# Sheet1.net
KiCad netlist of a schematic drawn in Altium Designer
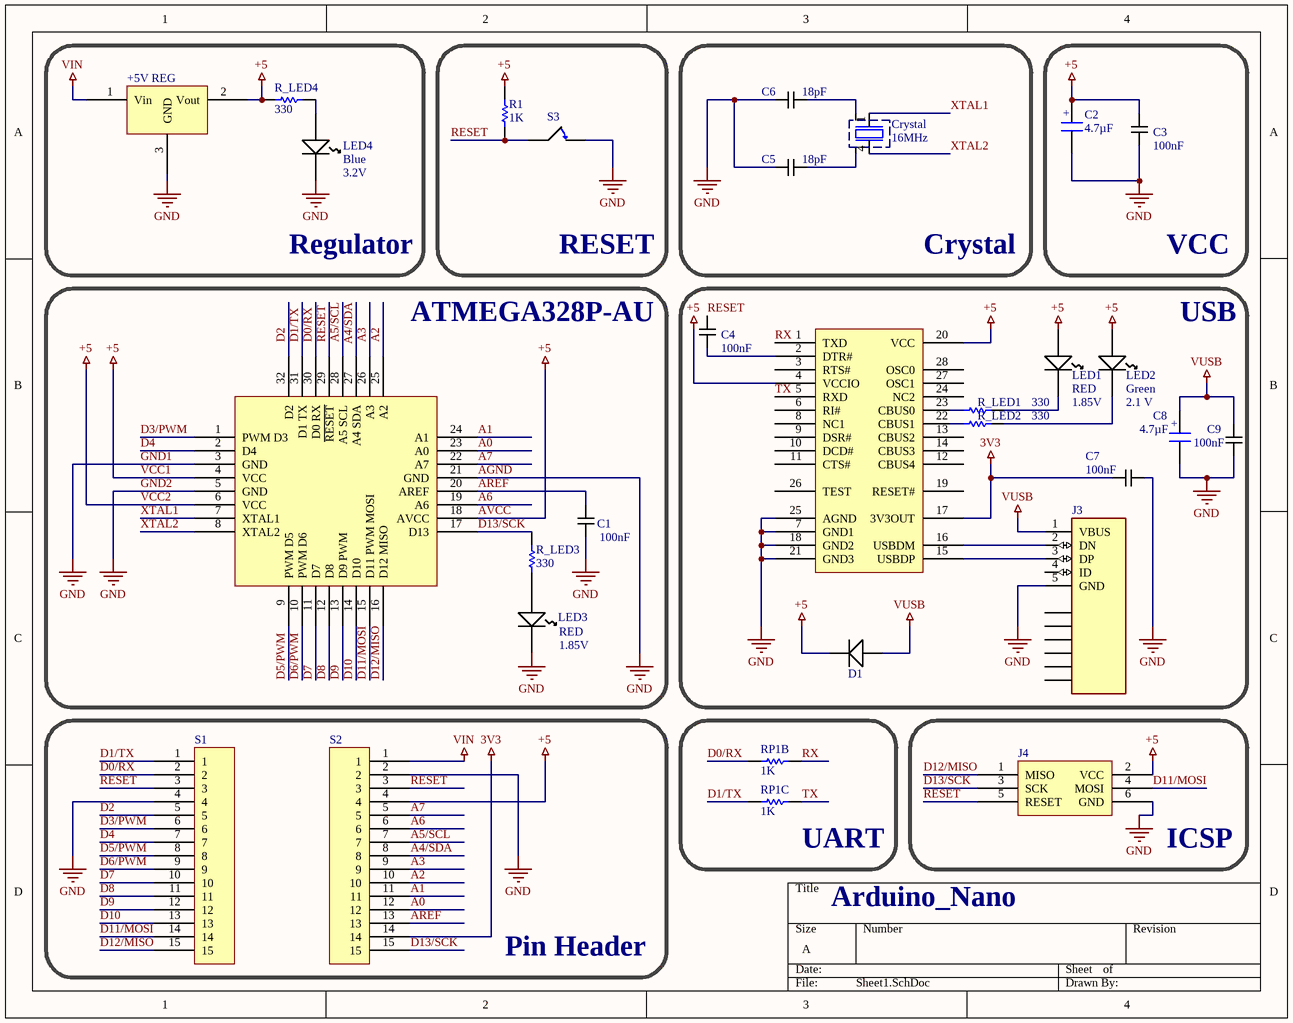
[diagram p0: Sheet1.SchDoc]

(export (version "E")
  (design (tool "Eeschema 10.0.6"))
  (components
    (comp (ref "+5V REG")
      (value "LM1117MP-5.0/NOPB, Low Dropout Voltage Regulator, 1.5A, 5 V ±1%, 4-Pin SOT-223")
      (footprint "SOT230P700X180-4N")
      (fields (field (name "MANUFACTURER") "Texas Instruments") (field (name "CREATED BY") "R Kanjee"))
      (libsource (lib "TI Low Dropout Voltage Regulator") (part "LM1117MP-5.0"))
    )
    (comp (ref "C1")
      (value "100nF Ceramic Multilayer Capacitor_1")
      (footprint "CAPCP2012X09N")
      (description "AVX 0805 Standard 100nF Ceramic Multilayer Capacitor, 50 V dc X7R Dielectric ±10% SMD")
      (fields
        (field (name "MANUFACTURER") "AVX")
        (field (name "VOLTAGE") "50V")
        (field (name "CAPACITANCE") "100nF")
        (field (name "CREATOR") "Ritesh Kanjee")
      )
      (libsource (lib "RS Components - Capacitors") (part "100nF Ceramic Multilayer Capacitor_1"))
    )
    (comp (ref "C2")
      (value "4.7µF")
      (footprint "CASE A - 3216X18")
      (description "Capacitor,tantalum,SMT,16V,4.7uF,10%,A-case")
      (fields
        (field (name "TOLERANCE") "10%")
        (field (name "VOLTAGE") "16V")
        (field (name "PUBLISHER") "DPSS")
      )
      (libsource (lib "RS Components - Capacitors") (part "4.7µF Tant RS 496-3545"))
    )
    (comp (ref "C3")
      (value "100nF Ceramic Multilayer Capacitor_1")
      (footprint "CAPCP2012X09N")
      (description "AVX 0805 Standard 100nF Ceramic Multilayer Capacitor, 50 V dc X7R Dielectric ±10% SMD")
      (fields
        (field (name "MANUFACTURER") "AVX")
        (field (name "VOLTAGE") "50V")
        (field (name "CAPACITANCE") "100nF")
        (field (name "CREATOR") "Ritesh Kanjee")
      )
      (libsource (lib "RS Components - Capacitors") (part "100nF Ceramic Multilayer Capacitor_1"))
    )
    (comp (ref "C4")
      (value "100nF Ceramic Multilayer Capacitor_1")
      (footprint "CAPCP2012X09N")
      (description "AVX 0805 Standard 100nF Ceramic Multilayer Capacitor, 50 V dc X7R Dielectric ±10% SMD")
      (fields
        (field (name "MANUFACTURER") "AVX")
        (field (name "VOLTAGE") "50V")
        (field (name "CAPACITANCE") "100nF")
        (field (name "CREATOR") "Ritesh Kanjee")
      )
      (libsource (lib "RS Components - Capacitors") (part "100nF Ceramic Multilayer Capacitor_1"))
    )
    (comp (ref "C5")
      (value "C0805C180J5GACTU")
      (footprint "CAPCP2012X09N")
      (description "18pF Ceramic Multilayer Capacitor, 50 V dc C0G Dielectric ±5% SMD")
      (fields
        (field (name "MANUFACTURER") "Kemet")
        (field (name "VOLTAGE") "50V")
        (field (name "CAPACITANCE") "18pF")
        (field (name "CREATOR") "Ritesh Kanjee")
      )
      (libsource (lib "RS Components - Capacitors") (part "18pF Ceramic Multilayer Capacitor, 50 V dc C0G Dielectric ±5% SMD"))
    )
    (comp (ref "C6")
      (value "C0805C180J5GACTU")
      (footprint "CAPCP2012X09N")
      (description "18pF Ceramic Multilayer Capacitor, 50 V dc C0G Dielectric ±5% SMD")
      (fields
        (field (name "MANUFACTURER") "Kemet")
        (field (name "VOLTAGE") "50V")
        (field (name "CAPACITANCE") "18pF")
        (field (name "CREATOR") "Ritesh Kanjee")
      )
      (libsource (lib "RS Components - Capacitors") (part "18pF Ceramic Multilayer Capacitor, 50 V dc C0G Dielectric ±5% SMD"))
    )
    (comp (ref "C7")
      (value "100nF Ceramic Multilayer Capacitor_1")
      (footprint "CAPCP2012X09N")
      (description "AVX 0805 Standard 100nF Ceramic Multilayer Capacitor, 50 V dc X7R Dielectric ±10% SMD")
      (fields
        (field (name "MANUFACTURER") "AVX")
        (field (name "VOLTAGE") "50V")
        (field (name "CAPACITANCE") "100nF")
        (field (name "CREATOR") "Ritesh Kanjee")
      )
      (libsource (lib "RS Components - Capacitors") (part "100nF Ceramic Multilayer Capacitor_1"))
    )
    (comp (ref "C8")
      (value "4.7µF")
      (footprint "CASE A - 3216X18")
      (description "Capacitor,tantalum,SMT,16V,4.7uF,10%,A-case")
      (fields
        (field (name "TOLERANCE") "10%")
        (field (name "VOLTAGE") "16V")
        (field (name "PUBLISHER") "DPSS")
      )
      (libsource (lib "RS Components - Capacitors") (part "4.7µF Tant RS 496-3545"))
    )
    (comp (ref "C9")
      (value "100nF Ceramic Multilayer Capacitor_1")
      (footprint "CAPCP2012X09N")
      (description "AVX 0805 Standard 100nF Ceramic Multilayer Capacitor, 50 V dc X7R Dielectric ±10% SMD")
      (fields
        (field (name "MANUFACTURER") "AVX")
        (field (name "VOLTAGE") "50V")
        (field (name "CAPACITANCE") "100nF")
        (field (name "CREATOR") "Ritesh Kanjee")
      )
      (libsource (lib "RS Components - Capacitors") (part "100nF Ceramic Multilayer Capacitor_1"))
    )
    (comp (ref "Crystal")
      (value "16MHz")
      (footprint "Aker S5C Crystal")
      (description "Aker S5C SMT Crystal")
      (fields
        (field (name "MANUFACTURER") "Aker")
        (field (name "MANUFACTURER PART #") "C5S-16.000-12-3030-X")
        (field (name "CREATOR") "R Kanjee")
      )
      (libsource (lib "Aker Crystals") (part "Aker  C5S-16.000-12-3030-X"))
    )
    (comp (ref "D1")
      (value "Panasonic DB2J20900L Schottky Diode, 0.5A, 20V, 2.4ns, 2-Pin SMini2 F5 B")
      (footprint "DIOM1712X07N")
      (fields
        (field (name "MANUFACTURER") "Panasonic")
        (field (name "MANUFACTURER PART NO.") "DB2J20900L")
        (field (name "CREATED BY") "R Kanjee")
      )
      (libsource (lib "Panasonic Diodes") (part "Schottky Diode, 0.5A, 20V, 2.4ns, 2-Pin SMini2 F5 B"))
    )
    (comp (ref "J3")
      (value "2013499-1")
      (footprint "TE_2013499-1")
      (libsource (lib "2013499-1") (part "2013499-1"))
    )
    (comp (ref "J4")
      (value "Programming Headers Dual Row")
      (footprint "ISP HEADER")
      (fields
        (field (name "MANUFACTURER") "FCI")
        (field (name "MANUFACTURER PART NO.") "68000-236HLF")
        (field (name "CREATED BY") "R Kanjee")
      )
      (libsource (lib "PCB Headers") (part "Programming ISP, Programming Headers Dual Row"))
    )
    (comp (ref "LED1")
      (value "Kingbright Red LED, 100 mcd 120 ° 0805")
      (footprint "LED1913X12NRED")
      (fields
        (field (name "MANUFACTURER") "KingBright")
        (field (name "MANUFACTURER PART NO.") "KP-2012SRC-PRV")
        (field (name "COLOR") "RED")
        (field (name "FORWARD VOLTAGE") "1.85V")
        (field (name "CREATOR") "Ritesh Kanjee")
      )
      (libsource (lib "KingBright LEDs") (part "Kingbright Red LED, 100 mcd 120 ° 0805"))
    )
    (comp (ref "LED2")
      (value "Kingbright Green LED, 70 mcd 120 ° 0805")
      (footprint "LED1913X12NGREEN")
      (fields
        (field (name "MANUFACTURER") "KingBright")
        (field (name "MANUFACTURER PART NO.") "KP-2012MGC")
        (field (name "COLOR") "Green")
        (field (name "FORWARD VOLTAGE") "2.1 V")
        (field (name "CREATOR") "Ritesh Kanjee")
      )
      (libsource (lib "KingBright LEDs") (part "Kingbright Green LED, 70 mcd 120 ° 0805"))
    )
    (comp (ref "LED3")
      (value "Kingbright Red LED, 100 mcd 120 ° 0805")
      (footprint "LED1913X12NRED")
      (fields
        (field (name "MANUFACTURER") "KingBright")
        (field (name "MANUFACTURER PART NO.") "KP-2012SRC-PRV")
        (field (name "COLOR") "RED")
        (field (name "FORWARD VOLTAGE") "1.85V")
        (field (name "CREATOR") "Ritesh Kanjee")
      )
      (libsource (lib "KingBright LEDs") (part "Kingbright Red LED, 100 mcd 120 ° 0805"))
    )
    (comp (ref "LED4")
      (value "Kingbright Blue LED, 60 mcd 120 ° 0805")
      (footprint "LED1913X12NBLUE")
      (fields
        (field (name "MANUFACTURER") "KingBright")
        (field (name "MANUFACTURER PART NO.") "KP-2012PBC-A")
        (field (name "COLOR") "Blue")
        (field (name "FORWARD VOLTAGE") "3.2V")
        (field (name "CREATOR") "Ritesh Kanjee")
      )
      (libsource (lib "KingBright LEDs") (part "Kingbright Blue LED, 60 mcd 120 ° 0805"))
    )
    (comp (ref "MicroController")
      (value "ATMEGA328P-AU")
      (footprint "TQFP80P900X900X120-32N")
      (description "ATMEGA328P-AU, 8 bit AVR Microcontroller 20MHz 1 kB, 32 kB Flash, 2 kB RAM, I2C 32-Pin TQFP")
      (fields (field (name "CREATED BY") "Ritesh Kanjee"))
      (libsource (lib "Atmel Microcontrollers") (part "ATMEGA328P-AU"))
    )
    (comp (ref "R1")
      (value "1K")
      (description "Resistor")
      (libsource (lib "Simulation Generic Components") (part "Resistor"))
    )
    (comp (ref "RP1B")
      (value "1K")
      (description "Resistor")
      (libsource (lib "Simulation Generic Components") (part "Resistor"))
    )
    (comp (ref "RP1C")
      (value "1K")
      (description "Resistor")
      (libsource (lib "Simulation Generic Components") (part "Resistor"))
    )
    (comp (ref "R_LED1")
      (value "330")
      (description "Resistor")
      (libsource (lib "Simulation Generic Components") (part "Resistor"))
    )
    (comp (ref "R_LED2")
      (value "330")
      (description "Resistor")
      (libsource (lib "Simulation Generic Components") (part "Resistor"))
    )
    (comp (ref "R_LED3")
      (value "330")
      (description "Resistor")
      (libsource (lib "Simulation Generic Components") (part "Resistor"))
    )
    (comp (ref "R_LED4")
      (value "330")
      (description "Resistor")
      (libsource (lib "Simulation Generic Components") (part "Resistor"))
    )
    (comp (ref "S1")
      (value "connector;str header;single row;.1 cont centers;.095 tail;gold or gtx;36 contact")
      (footprint "Header")
      (fields
        (field (name "MANUFACTURER") "FCI")
        (field (name "MANUFACTURER PART NO.") "68000-236HLF")
        (field (name "CREATED BY") "R Kanjee")
      )
      (libsource (lib "") (part "Single row; PCB headers_1"))
    )
    (comp (ref "S2")
      (value "connector;str header;single row;.1 cont centers;.095 tail;gold or gtx;36 contact")
      (footprint "Header")
      (fields
        (field (name "MANUFACTURER") "FCI")
        (field (name "MANUFACTURER PART NO.") "68000-236HLF")
        (field (name "CREATED BY") "R Kanjee")
      )
      (libsource (lib "PCB Headers") (part "Single row; PCB headers"))
    )
    (comp (ref "S3")
      (value "Button Tactile Switch, NO 0.05 A 0.8mm")
      (footprint "Button8014X17N")
      (fields
        (field (name "MANUFACTURER") "C & K")
        (field (name "MANUFACTURER PART NO.") "B3F1000")
        (field (name "CREATOR") "R Kanjee")
      )
      (libsource (lib "Omron Tactile Switches") (part "Button Tactile Switch, NO 0.05 A 0.8mm"))
    )
    (comp (ref "USB")
      (value "FT232RL, Universal Asynchronous Receiver & Transmitter 3MBd, 28-Pin, SSOP")
      (footprint "SOP65P780X200-28N")
      (fields
        (field (name "MANUFACTURER PART NO.") "FT232RL")
        (field (name "MANUFACTURER") "FTDI Chip")
        (field (name "CREATOR") "R Kanjee")
      )
      (libsource (lib "FTDI RS232toUSB") (part "FT232RL USB to UART, Universal Asynchronous Receiver & Transmitter 3MBd, 28-Pin, SSOP"))
    )
  )
  (nets
    (net (code "1") (name "+5") (class "Default")
      (node (ref "+5V REG") (pin "2") (pinfunction "Vout_2") (pintype "passive"))
      (node (ref "C2") (pin "1") (pinfunction "1_1") (pintype "passive"))
      (node (ref "C3") (pin "2") (pinfunction "2_2") (pintype "passive"))
      (node (ref "D1") (pin "1") (pinfunction "1_1") (pintype "passive"))
      (node (ref "J4") (pin "2") (pinfunction "VCC_2") (pintype "passive"))
      (node (ref "LED1") (pin "1") (pinfunction "A_1") (pintype "passive"))
      (node (ref "LED2") (pin "1") (pinfunction "A_1") (pintype "passive"))
      (node (ref "MicroController") (pin "18") (pinfunction "AVCC_18") (pintype "passive"))
      (node (ref "MicroController") (pin "4") (pinfunction "VCC_4") (pintype "passive"))
      (node (ref "MicroController") (pin "6") (pinfunction "VCC_6") (pintype "passive"))
      (node (ref "R1") (pin "2") (pinfunction "2_2") (pintype "passive"))
      (node (ref "R_LED4") (pin "1") (pinfunction "1_1") (pintype "passive"))
      (node (ref "S2") (pin "4") (pinfunction "4_4") (pintype "passive"))
      (node (ref "USB") (pin "20") (pinfunction "VCC_20") (pintype "passive"))
      (node (ref "USB") (pin "4") (pinfunction "VCCIO_4") (pintype "passive"))
    )
    (net (code "2") (name "/A0") (class "Default")
      (node (ref "MicroController") (pin "23") (pinfunction "A0_23") (pintype "passive"))
      (node (ref "S2") (pin "12") (pinfunction "12_12") (pintype "passive"))
    )
    (net (code "3") (name "/A1") (class "Default")
      (node (ref "MicroController") (pin "24") (pinfunction "A1_24") (pintype "passive"))
      (node (ref "S2") (pin "11") (pinfunction "11_11") (pintype "passive"))
    )
    (net (code "4") (name "/A2") (class "Default")
      (node (ref "MicroController") (pin "25") (pinfunction "A2_25") (pintype "passive"))
      (node (ref "S2") (pin "10") (pinfunction "10_10") (pintype "passive"))
    )
    (net (code "5") (name "/A3") (class "Default")
      (node (ref "MicroController") (pin "26") (pinfunction "A3_26") (pintype "passive"))
      (node (ref "S2") (pin "9") (pinfunction "9_9") (pintype "passive"))
    )
    (net (code "6") (name "/A4{slash}SDA") (class "Default")
      (node (ref "MicroController") (pin "27") (pinfunction "A4_SDA_27") (pintype "passive"))
      (node (ref "S2") (pin "8") (pinfunction "8_8") (pintype "passive"))
    )
    (net (code "7") (name "/A5{slash}SCL") (class "Default")
      (node (ref "MicroController") (pin "28") (pinfunction "A5_SCL_28") (pintype "passive"))
      (node (ref "S2") (pin "7") (pinfunction "7_7") (pintype "passive"))
    )
    (net (code "8") (name "/A6") (class "Default")
      (node (ref "MicroController") (pin "19") (pinfunction "A6_19") (pintype "passive"))
      (node (ref "S2") (pin "6") (pinfunction "6_6") (pintype "passive"))
    )
    (net (code "9") (name "/A7") (class "Default")
      (node (ref "MicroController") (pin "22") (pinfunction "A7_22") (pintype "passive"))
      (node (ref "S2") (pin "5") (pinfunction "5_5") (pintype "passive"))
    )
    (net (code "10") (name "/AREF") (class "Default")
      (node (ref "C1") (pin "2") (pinfunction "2_2") (pintype "passive"))
      (node (ref "MicroController") (pin "20") (pinfunction "AREF_20") (pintype "passive"))
      (node (ref "S2") (pin "13") (pinfunction "13_13") (pintype "passive"))
    )
    (net (code "11") (name "/D0{slash}RX") (class "Default")
      (node (ref "MicroController") (pin "30") (pinfunction "D0_RX_30") (pintype "passive"))
      (node (ref "RP1B") (pin "1") (pinfunction "1_1") (pintype "passive"))
      (node (ref "S1") (pin "2") (pinfunction "2_2") (pintype "passive"))
    )
    (net (code "12") (name "/D1{slash}TX") (class "Default")
      (node (ref "MicroController") (pin "31") (pinfunction "D1_TX_31") (pintype "passive"))
      (node (ref "RP1C") (pin "1") (pinfunction "1_1") (pintype "passive"))
      (node (ref "S1") (pin "1") (pinfunction "1_1") (pintype "passive"))
    )
    (net (code "13") (name "/D2") (class "Default")
      (node (ref "MicroController") (pin "32") (pinfunction "D2_32") (pintype "passive"))
      (node (ref "S1") (pin "5") (pinfunction "5_5") (pintype "passive"))
    )
    (net (code "14") (name "/D3{slash}PWM") (class "Default")
      (node (ref "MicroController") (pin "1") (pinfunction "PWM_D3_1") (pintype "passive"))
      (node (ref "S1") (pin "6") (pinfunction "6_6") (pintype "passive"))
    )
    (net (code "15") (name "/D4") (class "Default")
      (node (ref "MicroController") (pin "2") (pinfunction "D4_2") (pintype "passive"))
      (node (ref "S1") (pin "7") (pinfunction "7_7") (pintype "passive"))
    )
    (net (code "16") (name "/D5{slash}PWM") (class "Default")
      (node (ref "MicroController") (pin "9") (pinfunction "PWM_D5_9") (pintype "passive"))
      (node (ref "S1") (pin "8") (pinfunction "8_8") (pintype "passive"))
    )
    (net (code "17") (name "/D6{slash}PWM") (class "Default")
      (node (ref "MicroController") (pin "10") (pinfunction "PWM_D6_10") (pintype "passive"))
      (node (ref "S1") (pin "9") (pinfunction "9_9") (pintype "passive"))
    )
    (net (code "18") (name "/D7") (class "Default")
      (node (ref "MicroController") (pin "11") (pinfunction "D7_11") (pintype "passive"))
      (node (ref "S1") (pin "10") (pinfunction "10_10") (pintype "passive"))
    )
    (net (code "19") (name "/D8") (class "Default")
      (node (ref "MicroController") (pin "12") (pinfunction "D8_12") (pintype "passive"))
      (node (ref "S1") (pin "11") (pinfunction "11_11") (pintype "passive"))
    )
    (net (code "20") (name "/D9") (class "Default")
      (node (ref "MicroController") (pin "13") (pinfunction "D9_PWM_13") (pintype "passive"))
      (node (ref "S1") (pin "12") (pinfunction "12_12") (pintype "passive"))
    )
    (net (code "21") (name "/D10") (class "Default")
      (node (ref "MicroController") (pin "14") (pinfunction "D10_14") (pintype "passive"))
      (node (ref "S1") (pin "13") (pinfunction "13_13") (pintype "passive"))
    )
    (net (code "22") (name "/D11{slash}MOSI") (class "Default")
      (node (ref "J4") (pin "4") (pinfunction "MOSI_4") (pintype "passive"))
      (node (ref "MicroController") (pin "15") (pinfunction "D11_PWM_MOSI_15") (pintype "passive"))
      (node (ref "S1") (pin "14") (pinfunction "14_14") (pintype "passive"))
    )
    (net (code "23") (name "/D12{slash}MISO") (class "Default")
      (node (ref "J4") (pin "1") (pinfunction "MISO_1") (pintype "passive"))
      (node (ref "MicroController") (pin "16") (pinfunction "D12_MISO_16") (pintype "passive"))
      (node (ref "S1") (pin "15") (pinfunction "15_15") (pintype "passive"))
    )
    (net (code "24") (name "/D13{slash}SCK") (class "Default")
      (node (ref "J4") (pin "3") (pinfunction "SCK_3") (pintype "passive"))
      (node (ref "MicroController") (pin "17") (pinfunction "D13_17") (pintype "passive"))
      (node (ref "R_LED3") (pin "2") (pinfunction "2_2") (pintype "passive"))
      (node (ref "S2") (pin "15") (pinfunction "15_15") (pintype "passive"))
    )
    (net (code "25") (name "/RESET") (class "Default")
      (node (ref "C4") (pin "2") (pinfunction "2_2") (pintype "passive"))
      (node (ref "J4") (pin "5") (pinfunction "RESET_5") (pintype "passive"))
      (node (ref "MicroController") (pin "29") (pinfunction "~{RESET}_29") (pintype "passive"))
      (node (ref "R1") (pin "1") (pinfunction "1_1") (pintype "passive"))
      (node (ref "S1") (pin "3") (pinfunction "3_3") (pintype "passive"))
      (node (ref "S2") (pin "3") (pinfunction "3_3") (pintype "passive"))
      (node (ref "S3") (pin "1") (pinfunction "1_1") (pintype "passive"))
    )
    (net (code "26") (name "/RX") (class "Default")
      (node (ref "RP1B") (pin "2") (pinfunction "2_2") (pintype "passive"))
      (node (ref "USB") (pin "1") (pinfunction "TXD_1") (pintype "passive"))
    )
    (net (code "27") (name "/TX") (class "Default")
      (node (ref "RP1C") (pin "2") (pinfunction "2_2") (pintype "passive"))
      (node (ref "USB") (pin "5") (pinfunction "RXD_5") (pintype "passive"))
    )
    (net (code "28") (name "/XTAL1") (class "Default")
      (node (ref "Crystal") (pin "1") (pinfunction "1_1") (pintype "passive"))
      (node (ref "MicroController") (pin "7") (pinfunction "XTAL1_7") (pintype "passive"))
    )
    (net (code "29") (name "/XTAL2") (class "Default")
      (node (ref "Crystal") (pin "4") (pinfunction "4_4") (pintype "passive"))
      (node (ref "MicroController") (pin "8") (pinfunction "XTAL2_8") (pintype "passive"))
    )
    (net (code "30") (name "3V3") (class "Default")
      (node (ref "C7") (pin "1") (pinfunction "1_1") (pintype "passive"))
      (node (ref "S2") (pin "14") (pinfunction "14_14") (pintype "passive"))
      (node (ref "USB") (pin "17") (pinfunction "3V3OUT_17") (pintype "passive"))
    )
    (net (code "31") (name "GND") (class "Default")
      (node (ref "+5V REG") (pin "3") (pinfunction "GND_3") (pintype "passive"))
      (node (ref "C1") (pin "1") (pinfunction "1_1") (pintype "passive"))
      (node (ref "C2") (pin "2") (pinfunction "2_2") (pintype "passive"))
      (node (ref "C3") (pin "1") (pinfunction "1_1") (pintype "passive"))
      (node (ref "C5") (pin "2") (pinfunction "2_2") (pintype "passive"))
      (node (ref "C6") (pin "2") (pinfunction "2_2") (pintype "passive"))
      (node (ref "C7") (pin "2") (pinfunction "2_2") (pintype "passive"))
      (node (ref "C8") (pin "2") (pinfunction "2_2") (pintype "passive"))
      (node (ref "C9") (pin "1") (pinfunction "1_1") (pintype "passive"))
      (node (ref "J3") (pin "5") (pinfunction "GND_5") (pintype "power_in"))
      (node (ref "J4") (pin "6") (pinfunction "GND_6") (pintype "passive"))
      (node (ref "LED3") (pin "2") (pinfunction "K_2") (pintype "passive"))
      (node (ref "LED4") (pin "2") (pinfunction "K_2") (pintype "passive"))
      (node (ref "MicroController") (pin "21") (pinfunction "GND_21") (pintype "passive"))
      (node (ref "MicroController") (pin "3") (pinfunction "GND_3") (pintype "passive"))
      (node (ref "MicroController") (pin "5") (pinfunction "GND_5") (pintype "passive"))
      (node (ref "S1") (pin "4") (pinfunction "4_4") (pintype "passive"))
      (node (ref "S2") (pin "2") (pinfunction "2_2") (pintype "passive"))
      (node (ref "S3") (pin "1") (pinfunction "1_1") (pintype "passive"))
      (node (ref "USB") (pin "18") (pinfunction "GND2_18") (pintype "passive"))
      (node (ref "USB") (pin "21") (pinfunction "GND3_21") (pintype "passive"))
      (node (ref "USB") (pin "25") (pinfunction "AGND_25") (pintype "passive"))
      (node (ref "USB") (pin "7") (pinfunction "GND1_7") (pintype "passive"))
    )
    (net (code "32") (name "Net-(C5-Pad1)") (class "Default")
      (node (ref "C5") (pin "1") (pinfunction "1_1") (pintype "passive"))
      (node (ref "Crystal") (pin "2") (pinfunction "Gnd_2") (pintype "power_in"))
    )
    (net (code "33") (name "Net-(C6-Pad1)") (class "Default")
      (node (ref "C6") (pin "1") (pinfunction "1_1") (pintype "passive"))
      (node (ref "Crystal") (pin "3") (pinfunction "Gnd_3") (pintype "power_in"))
    )
    (net (code "34") (name "Net-(J3-DN)") (class "Default")
      (node (ref "J3") (pin "2") (pinfunction "DN_2") (pintype "bidirectional"))
      (node (ref "USB") (pin "16") (pinfunction "USBDM_16") (pintype "passive"))
    )
    (net (code "35") (name "Net-(J3-DP)") (class "Default")
      (node (ref "J3") (pin "3") (pinfunction "DP_3") (pintype "bidirectional"))
      (node (ref "USB") (pin "15") (pinfunction "USBDP_15") (pintype "passive"))
    )
    (net (code "36") (name "Net-(LED1-K)") (class "Default")
      (node (ref "LED1") (pin "2") (pinfunction "K_2") (pintype "passive"))
      (node (ref "R_LED1") (pin "1") (pinfunction "1_1") (pintype "passive"))
    )
    (net (code "37") (name "Net-(LED2-K)") (class "Default")
      (node (ref "LED2") (pin "2") (pinfunction "K_2") (pintype "passive"))
      (node (ref "R_LED2") (pin "1") (pinfunction "1_1") (pintype "passive"))
    )
    (net (code "38") (name "Net-(LED3-A)") (class "Default")
      (node (ref "LED3") (pin "1") (pinfunction "A_1") (pintype "passive"))
      (node (ref "R_LED3") (pin "1") (pinfunction "1_1") (pintype "passive"))
    )
    (net (code "39") (name "Net-(LED4-A)") (class "Default")
      (node (ref "LED4") (pin "1") (pinfunction "A_1") (pintype "passive"))
      (node (ref "R_LED4") (pin "2") (pinfunction "2_2") (pintype "passive"))
    )
    (net (code "40") (name "Net-(USB-CBUS0)") (class "Default")
      (node (ref "R_LED1") (pin "2") (pinfunction "2_2") (pintype "passive"))
      (node (ref "USB") (pin "23") (pinfunction "CBUS0_23") (pintype "passive"))
    )
    (net (code "41") (name "Net-(USB-CBUS1)") (class "Default")
      (node (ref "R_LED2") (pin "2") (pinfunction "2_2") (pintype "passive"))
      (node (ref "USB") (pin "22") (pinfunction "CBUS1_22") (pintype "passive"))
    )
    (net (code "42") (name "Net-(USB-DTR#)") (class "Default")
      (node (ref "C4") (pin "1") (pinfunction "1_1") (pintype "passive"))
      (node (ref "USB") (pin "2") (pinfunction "DTR#_2") (pintype "passive"))
    )
    (net (code "43") (name "VIN") (class "Default")
      (node (ref "+5V REG") (pin "1") (pinfunction "Vin_1") (pintype "passive"))
      (node (ref "S2") (pin "1") (pinfunction "1_1") (pintype "passive"))
    )
    (net (code "44") (name "VUSB") (class "Default")
      (node (ref "C8") (pin "1") (pinfunction "1_1") (pintype "passive"))
      (node (ref "C9") (pin "2") (pinfunction "2_2") (pintype "passive"))
      (node (ref "D1") (pin "2") (pinfunction "2_2") (pintype "passive"))
      (node (ref "J3") (pin "1") (pinfunction "VBUS_1") (pintype "power_in"))
    )
    (net (code "45") (name "unconnected-(J3-ID-Pad4)") (class "Default")
      (node (ref "J3") (pin "4") (pinfunction "ID_4") (pintype "bidirectional"))
    )
    (net (code "46") (name "unconnected-(J3-SHIELD-PadSH1)") (class "Default")
      (node (ref "J3") (pin "SH1") (pinfunction "SHIELD_SH1") (pintype "passive"))
    )
    (net (code "47") (name "unconnected-(J3-SHIELD-PadSH2)") (class "Default")
      (node (ref "J3") (pin "SH2") (pinfunction "SHIELD_SH2") (pintype "passive"))
    )
    (net (code "48") (name "unconnected-(J3-SHIELD-PadSH3)") (class "Default")
      (node (ref "J3") (pin "SH3") (pinfunction "SHIELD_SH3") (pintype "passive"))
    )
    (net (code "49") (name "unconnected-(J3-SHIELD-PadSH4)") (class "Default")
      (node (ref "J3") (pin "SH4") (pinfunction "SHIELD_SH4") (pintype "passive"))
    )
    (net (code "50") (name "unconnected-(J3-SHIELD-PadSH5)") (class "Default")
      (node (ref "J3") (pin "SH5") (pinfunction "SHIELD_SH5") (pintype "passive"))
    )
    (net (code "51") (name "unconnected-(J3-SHIELD-PadSH6)") (class "Default")
      (node (ref "J3") (pin "SH6") (pinfunction "SHIELD_SH6") (pintype "passive"))
    )
    (net (code "52") (name "unconnected-(USB-CBUS2-Pad13)") (class "Default")
      (node (ref "USB") (pin "13") (pinfunction "CBUS2_13") (pintype "passive"))
    )
    (net (code "53") (name "unconnected-(USB-CBUS3-Pad14)") (class "Default")
      (node (ref "USB") (pin "14") (pinfunction "CBUS3_14") (pintype "passive"))
    )
    (net (code "54") (name "unconnected-(USB-CBUS4-Pad12)") (class "Default")
      (node (ref "USB") (pin "12") (pinfunction "CBUS4_12") (pintype "passive"))
    )
    (net (code "55") (name "unconnected-(USB-CTS#-Pad11)") (class "Default")
      (node (ref "USB") (pin "11") (pinfunction "CTS#_11") (pintype "passive"))
    )
    (net (code "56") (name "unconnected-(USB-DCD#-Pad10)") (class "Default")
      (node (ref "USB") (pin "10") (pinfunction "DCD#_10") (pintype "passive"))
    )
    (net (code "57") (name "unconnected-(USB-DSR#-Pad9)") (class "Default")
      (node (ref "USB") (pin "9") (pinfunction "DSR#_9") (pintype "passive"))
    )
    (net (code "58") (name "unconnected-(USB-NC1-Pad8)") (class "Default")
      (node (ref "USB") (pin "8") (pinfunction "NC1_8") (pintype "passive"))
    )
    (net (code "59") (name "unconnected-(USB-NC2-Pad24)") (class "Default")
      (node (ref "USB") (pin "24") (pinfunction "NC2_24") (pintype "passive"))
    )
    (net (code "60") (name "unconnected-(USB-OSC0-Pad28)") (class "Default")
      (node (ref "USB") (pin "28") (pinfunction "OSC0_28") (pintype "passive"))
    )
    (net (code "61") (name "unconnected-(USB-OSC1-Pad27)") (class "Default")
      (node (ref "USB") (pin "27") (pinfunction "OSC1_27") (pintype "passive"))
    )
    (net (code "62") (name "unconnected-(USB-RESET#-Pad19)") (class "Default")
      (node (ref "USB") (pin "19") (pinfunction "RESET#_19") (pintype "passive"))
    )
    (net (code "63") (name "unconnected-(USB-RI#-Pad6)") (class "Default")
      (node (ref "USB") (pin "6") (pinfunction "RI#_6") (pintype "passive"))
    )
    (net (code "64") (name "unconnected-(USB-RTS#-Pad3)") (class "Default")
      (node (ref "USB") (pin "3") (pinfunction "RTS#_3") (pintype "passive"))
    )
    (net (code "65") (name "unconnected-(USB-TEST-Pad26)") (class "Default")
      (node (ref "USB") (pin "26") (pinfunction "TEST_26") (pintype "passive"))
    )
  )
)
